# RobotCtrl_Base_Func.net
KiCad netlist of a schematic drawn in Altium Designer
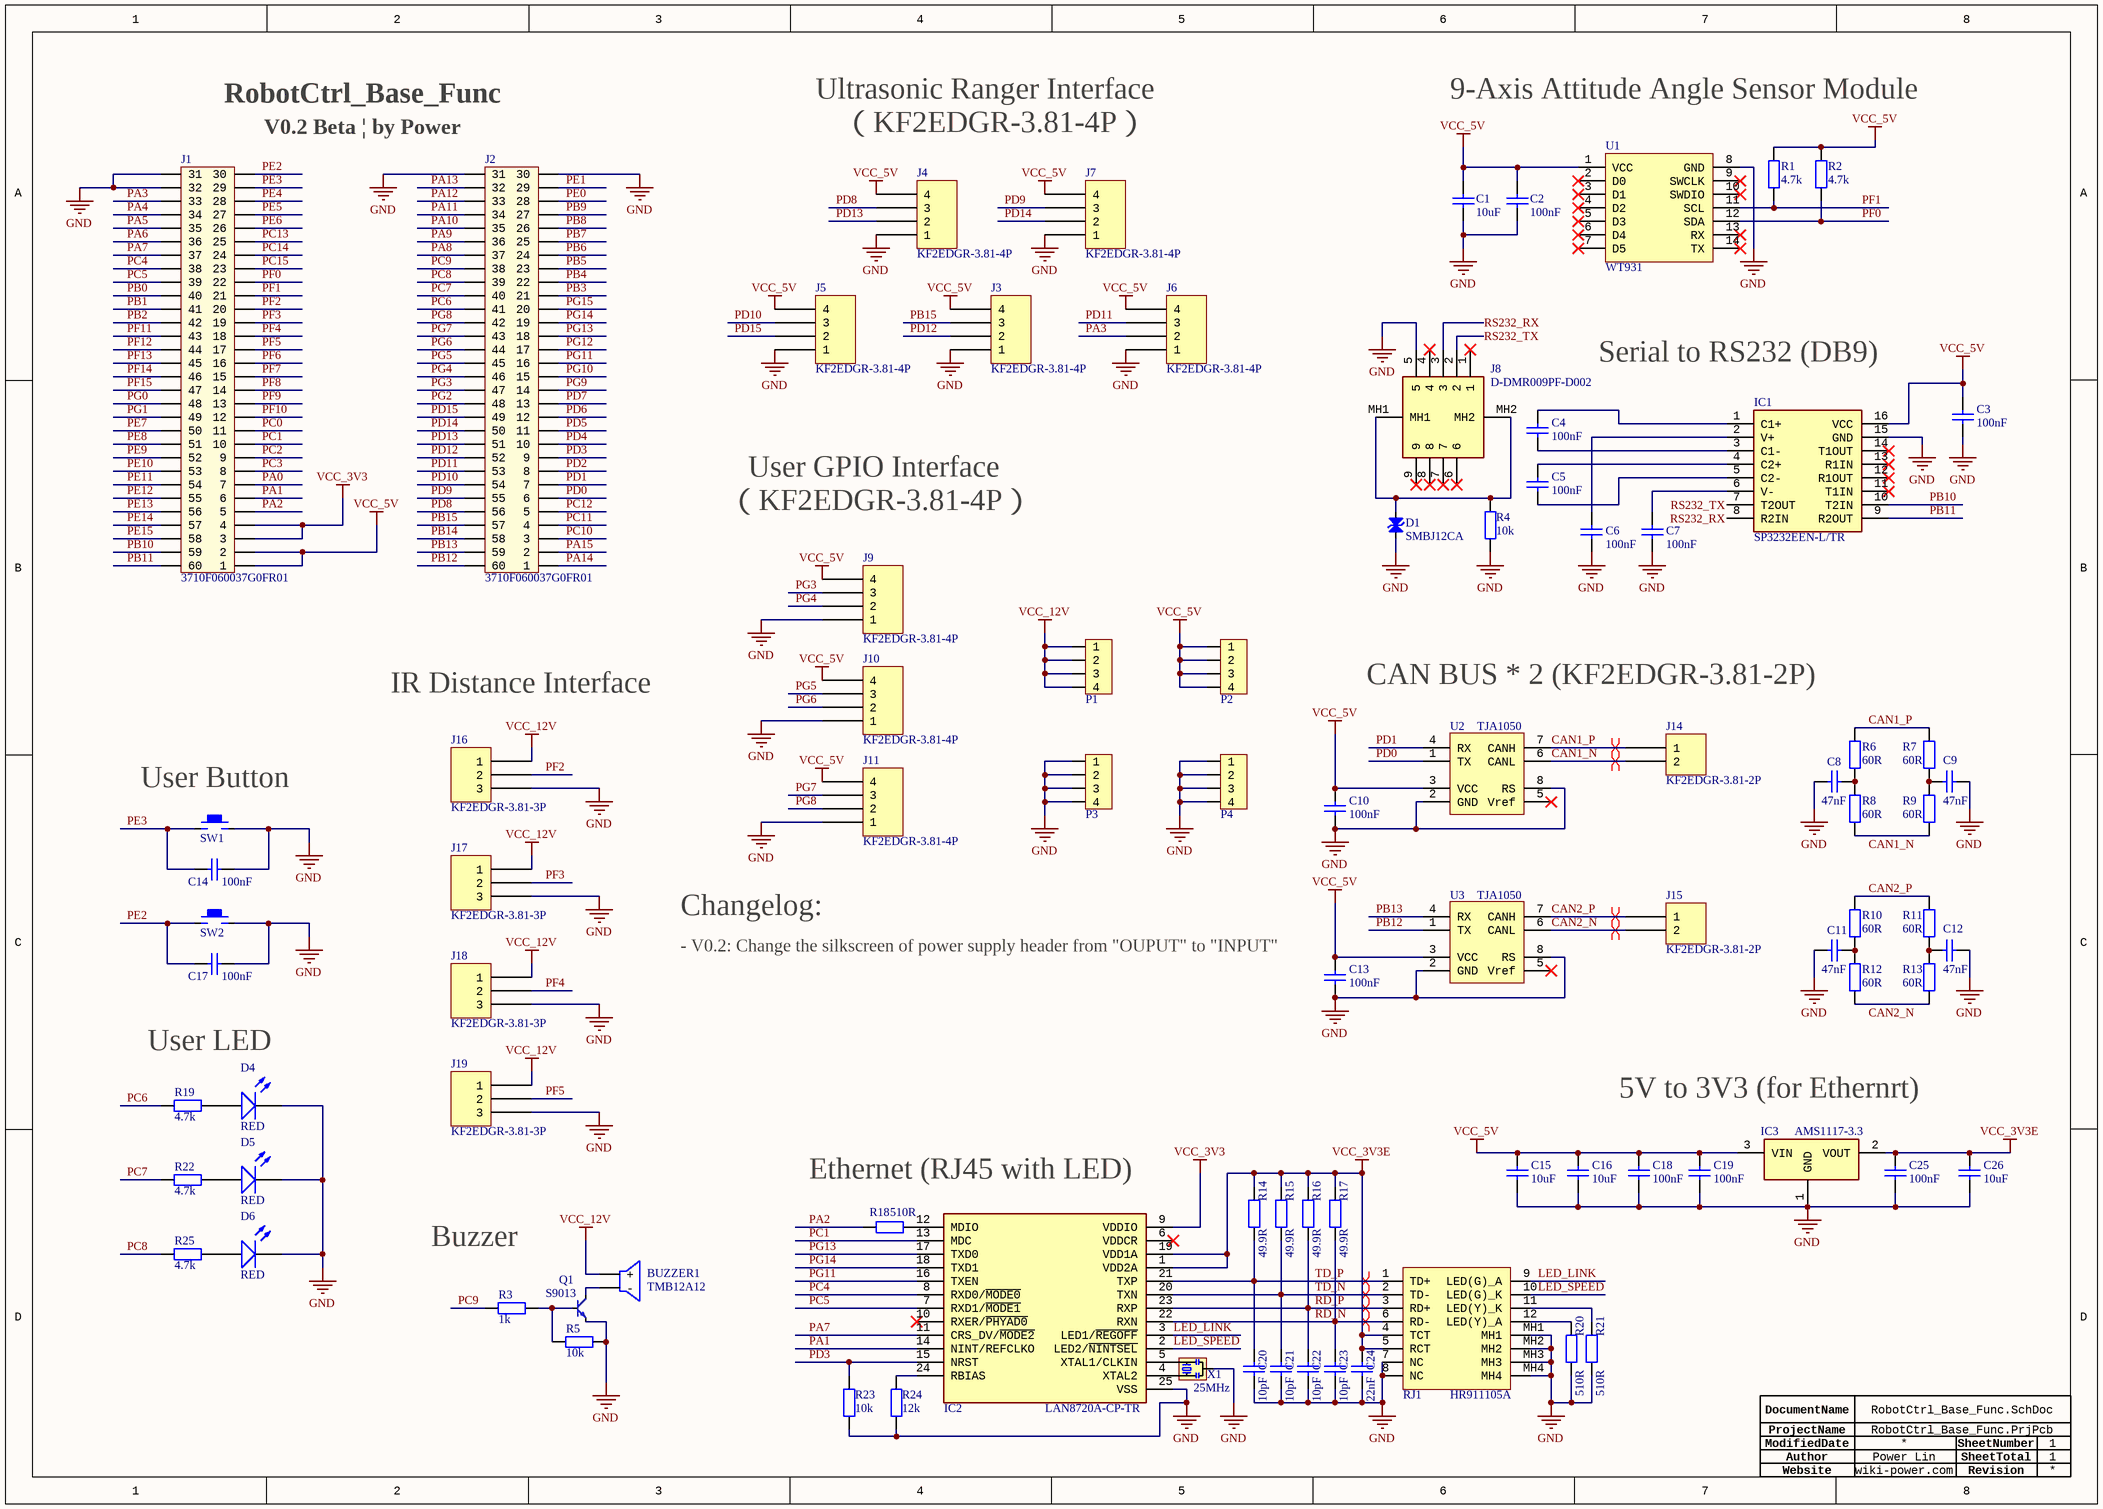
[diagram p0: RobotCtrl_Base_Func.SchDoc]

(export (version "E")
  (design (tool "Eeschema 10.0.6"))
  (components
    (comp (ref "BUZZER1")
      (value "TMB12A12")
      (footprint "DIP,P=7.6mm")
      (description "TMB12A12 有源蜂鸣器")
      (libsource (lib "Power_Lib_Altium") (part "BUZZER"))
    )
    (comp (ref "C1")
      (value "10uF")
      (footprint "CAP-0603")
      (description "贴片电容")
      (libsource (lib "Power_Lib_Altium") (part "CAP"))
    )
    (comp (ref "C2")
      (value "100nF")
      (footprint "CAP-0603")
      (description "贴片电容")
      (libsource (lib "Power_Lib_Altium") (part "CAP"))
    )
    (comp (ref "C3")
      (value "100nF")
      (footprint "CAP-0603")
      (description "贴片电容")
      (libsource (lib "Power_Lib_Altium") (part "CAP"))
    )
    (comp (ref "C4")
      (value "100nF")
      (footprint "CAP-0603")
      (description "贴片电容")
      (libsource (lib "Power_Lib_Altium") (part "CAP"))
    )
    (comp (ref "C5")
      (value "100nF")
      (footprint "CAP-0603")
      (description "贴片电容")
      (libsource (lib "Power_Lib_Altium") (part "CAP"))
    )
    (comp (ref "C6")
      (value "100nF")
      (footprint "CAP-0603")
      (description "贴片电容")
      (libsource (lib "Power_Lib_Altium") (part "CAP"))
    )
    (comp (ref "C7")
      (value "100nF")
      (footprint "CAP-0603")
      (description "贴片电容")
      (libsource (lib "Power_Lib_Altium") (part "CAP"))
    )
    (comp (ref "C8")
      (value "47nF")
      (footprint "CAP-0603")
      (description "贴片电容")
      (libsource (lib "Power_Lib_Altium") (part "CAP"))
    )
    (comp (ref "C9")
      (value "47nF")
      (footprint "CAP-0603")
      (description "贴片电容")
      (libsource (lib "Power_Lib_Altium") (part "CAP"))
    )
    (comp (ref "C10")
      (value "100nF")
      (footprint "CAP-0603")
      (description "贴片电容")
      (libsource (lib "Power_Lib_Altium") (part "CAP"))
    )
    (comp (ref "C11")
      (value "47nF")
      (footprint "CAP-0603")
      (description "贴片电容")
      (libsource (lib "Power_Lib_Altium") (part "CAP"))
    )
    (comp (ref "C12")
      (value "47nF")
      (footprint "CAP-0603")
      (description "贴片电容")
      (libsource (lib "Power_Lib_Altium") (part "CAP"))
    )
    (comp (ref "C13")
      (value "100nF")
      (footprint "CAP-0603")
      (description "贴片电容")
      (libsource (lib "Power_Lib_Altium") (part "CAP"))
    )
    (comp (ref "C14")
      (value "100nF")
      (footprint "CAP-0603")
      (description "贴片电容")
      (libsource (lib "Power_Lib_Altium") (part "CAP"))
    )
    (comp (ref "C15")
      (value "10uF")
      (footprint "CAP-0603")
      (description "贴片电容")
      (libsource (lib "Power_Lib_Altium") (part "CAP"))
    )
    (comp (ref "C16")
      (value "10uF")
      (footprint "CAP-0603")
      (description "贴片电容")
      (libsource (lib "Power_Lib_Altium") (part "CAP"))
    )
    (comp (ref "C17")
      (value "100nF")
      (footprint "CAP-0603")
      (description "贴片电容")
      (libsource (lib "Power_Lib_Altium") (part "CAP"))
    )
    (comp (ref "C18")
      (value "100nF")
      (footprint "CAP-0603")
      (description "贴片电容")
      (libsource (lib "Power_Lib_Altium") (part "CAP"))
    )
    (comp (ref "C19")
      (value "100nF")
      (footprint "CAP-0603")
      (description "贴片电容")
      (libsource (lib "Power_Lib_Altium") (part "CAP"))
    )
    (comp (ref "C20")
      (value "10pF")
      (footprint "CAP-0603")
      (description "贴片电容")
      (libsource (lib "Power_Lib_Altium") (part "CAP"))
    )
    (comp (ref "C21")
      (value "10pF")
      (footprint "CAP-0603")
      (description "贴片电容")
      (libsource (lib "Power_Lib_Altium") (part "CAP"))
    )
    (comp (ref "C22")
      (value "10pF")
      (footprint "CAP-0603")
      (description "贴片电容")
      (libsource (lib "Power_Lib_Altium") (part "CAP"))
    )
    (comp (ref "C23")
      (value "10pF")
      (footprint "CAP-0603")
      (description "贴片电容")
      (libsource (lib "Power_Lib_Altium") (part "CAP"))
    )
    (comp (ref "C24")
      (value "22nF")
      (footprint "CAP-0603")
      (description "贴片电容")
      (libsource (lib "Power_Lib_Altium") (part "CAP"))
    )
    (comp (ref "C25")
      (value "100nF")
      (footprint "CAP-0603")
      (description "贴片电容")
      (libsource (lib "Power_Lib_Altium") (part "CAP"))
    )
    (comp (ref "C26")
      (value "10uF")
      (footprint "CAP-0603")
      (description "贴片电容")
      (libsource (lib "Power_Lib_Altium") (part "CAP"))
    )
    (comp (ref "D1")
      (value "SMBJ12CA")
      (footprint "DO-214AA/SMB")
      (libsource (lib "Power_Lib_Altium") (part "TVS_C"))
    )
    (comp (ref "D4")
      (value "RED")
      (footprint "LED-0603")
      (description "发光二极管")
      (libsource (lib "Power_Lib_Altium") (part "LED"))
    )
    (comp (ref "D5")
      (value "RED")
      (footprint "LED-0603")
      (description "发光二极管")
      (libsource (lib "Power_Lib_Altium") (part "LED"))
    )
    (comp (ref "D6")
      (value "RED")
      (footprint "LED-0603")
      (description "发光二极管")
      (libsource (lib "Power_Lib_Altium") (part "LED"))
    )
    (comp (ref "IC1")
      (value "SP3232EEN-L/TR")
      (footprint "SOIC-16_150mil")
      (description "RS232 芯片")
      (fields (field (name "MOUSER PART NUMBER") "701-SP3232EEN-L/TR"))
      (libsource (lib "Power_Lib_Altium") (part "SP3232EEN"))
    )
    (comp (ref "IC2")
      (value "LAN8720A-CP-TR")
      (footprint "QFN-24-4x4")
      (description "Integrated Circuit")
      (fields (field (name "MOUSER PART NUMBER") "886-LAN8720A-CP-TR"))
      (libsource (lib "Power_Lib_Altium") (part "LAN8720A-CP-TR"))
    )
    (comp (ref "IC3")
      (value "AMS1117-3.3")
      (footprint "SOT-223")
      (description "AMS1117-3.3 1.0A")
      (fields (field (name "MANUFACTURER_PART_NUMBER") "SI2302DS") (field (name "RS PART NUMBER") "7983053P"))
      (libsource (lib "Power_Lib_Altium") (part "AMS1117"))
    )
    (comp (ref "J1")
      (value "3710F060037G0FR01")
      (footprint "3710M060037G3FT01")
      (description "B2B Connector")
      (libsource (lib "Power_Lib_Altium") (part "3710M/F"))
    )
    (comp (ref "J2")
      (value "3710F060037G0FR01")
      (footprint "3710M060037G3FT01")
      (description "B2B Connector")
      (libsource (lib "Power_Lib_Altium") (part "3710M/F"))
    )
    (comp (ref "J3")
      (value "KF2EDGR-3.81-4P")
      (footprint "FCI 06-381-4PIN")
      (description "TERM BLOCK HDR 4POS 90DEG 3.81MM")
      (fields (field (name "PART NUMBER") "OQ0432510000G") (field (name "MANUFACTURER") "Amphenol Anytek"))
      (libsource (lib "Power_Lib_Altium") (part "KF2EDGR-3.81-4P"))
    )
    (comp (ref "J4")
      (value "KF2EDGR-3.81-4P")
      (footprint "FCI 06-381-4PIN")
      (description "TERM BLOCK HDR 4POS 90DEG 3.81MM")
      (fields (field (name "PART NUMBER") "OQ0432510000G") (field (name "MANUFACTURER") "Amphenol Anytek"))
      (libsource (lib "Power_Lib_Altium") (part "KF2EDGR-3.81-4P"))
    )
    (comp (ref "J5")
      (value "KF2EDGR-3.81-4P")
      (footprint "FCI 06-381-4PIN")
      (description "TERM BLOCK HDR 4POS 90DEG 3.81MM")
      (fields (field (name "PART NUMBER") "OQ0432510000G") (field (name "MANUFACTURER") "Amphenol Anytek"))
      (libsource (lib "Power_Lib_Altium") (part "KF2EDGR-3.81-4P"))
    )
    (comp (ref "J6")
      (value "KF2EDGR-3.81-4P")
      (footprint "FCI 06-381-4PIN")
      (description "TERM BLOCK HDR 4POS 90DEG 3.81MM")
      (fields (field (name "PART NUMBER") "OQ0432510000G") (field (name "MANUFACTURER") "Amphenol Anytek"))
      (libsource (lib "Power_Lib_Altium") (part "KF2EDGR-3.81-4P"))
    )
    (comp (ref "J7")
      (value "KF2EDGR-3.81-4P")
      (footprint "FCI 06-381-4PIN")
      (description "TERM BLOCK HDR 4POS 90DEG 3.81MM")
      (fields (field (name "PART NUMBER") "OQ0432510000G") (field (name "MANUFACTURER") "Amphenol Anytek"))
      (libsource (lib "Power_Lib_Altium") (part "KF2EDGR-3.81-4P"))
    )
    (comp (ref "J8")
      (value "D-DMR009PF-D002")
      (footprint "Through Hole,P=2.77mm")
      (description "D-Sub 连接器")
      (fields
        (field (name "MANUFACTURER_PART_NUMBER") "5747844-5")
        (field (name "MOUSER PART NUMBER") "571-5747844-5")
      )
      (libsource (lib "Power_Lib_Altium") (part "DB9"))
    )
    (comp (ref "J9")
      (value "KF2EDGR-3.81-4P")
      (footprint "FCI 06-381-4PIN")
      (description "TERM BLOCK HDR 4POS 90DEG 3.81MM")
      (fields (field (name "PART NUMBER") "OQ0432510000G") (field (name "MANUFACTURER") "Amphenol Anytek"))
      (libsource (lib "Power_Lib_Altium") (part "KF2EDGR-3.81-4P"))
    )
    (comp (ref "J10")
      (value "KF2EDGR-3.81-4P")
      (footprint "FCI 06-381-4PIN")
      (description "TERM BLOCK HDR 4POS 90DEG 3.81MM")
      (fields (field (name "PART NUMBER") "OQ0432510000G") (field (name "MANUFACTURER") "Amphenol Anytek"))
      (libsource (lib "Power_Lib_Altium") (part "KF2EDGR-3.81-4P"))
    )
    (comp (ref "J11")
      (value "KF2EDGR-3.81-4P")
      (footprint "FCI 06-381-4PIN")
      (description "TERM BLOCK HDR 4POS 90DEG 3.81MM")
      (fields (field (name "PART NUMBER") "OQ0432510000G") (field (name "MANUFACTURER") "Amphenol Anytek"))
      (libsource (lib "Power_Lib_Altium") (part "KF2EDGR-3.81-4P"))
    )
    (comp (ref "J14")
      (value "KF2EDGR-3.81-2P")
      (footprint "FCI 06-381-2PIN")
      (description "TERM BLOCK HDR 2POS 90DEG 3.81MM")
      (fields (field (name "PART NUMBER") "OQ0232510000G") (field (name "MANUFACTURER") "Amphenol Anytek"))
      (libsource (lib "Power_Lib_Altium") (part "KF2EDGR-3.81-2P"))
    )
    (comp (ref "J15")
      (value "KF2EDGR-3.81-2P")
      (footprint "FCI 06-381-2PIN")
      (description "TERM BLOCK HDR 2POS 90DEG 3.81MM")
      (fields (field (name "PART NUMBER") "OQ0232510000G") (field (name "MANUFACTURER") "Amphenol Anytek"))
      (libsource (lib "Power_Lib_Altium") (part "KF2EDGR-3.81-2P"))
    )
    (comp (ref "J16")
      (value "KF2EDGR-3.81-3P")
      (footprint "FCI 06-381-3PIN")
      (description "TERM BLOCK HDR 3POS 90DEG 3.81MM")
      (fields (field (name "MANUFACTURER") "Amphenol Anytek") (field (name "PART NUMBER") "OQ0332510000G"))
      (libsource (lib "Power_Lib_Altium") (part "KF2EDGR-3.81-3P"))
    )
    (comp (ref "J17")
      (value "KF2EDGR-3.81-3P")
      (footprint "FCI 06-381-3PIN")
      (description "TERM BLOCK HDR 3POS 90DEG 3.81MM")
      (fields (field (name "MANUFACTURER") "Amphenol Anytek") (field (name "PART NUMBER") "OQ0332510000G"))
      (libsource (lib "Power_Lib_Altium") (part "KF2EDGR-3.81-3P"))
    )
    (comp (ref "J18")
      (value "KF2EDGR-3.81-3P")
      (footprint "FCI 06-381-3PIN")
      (description "TERM BLOCK HDR 3POS 90DEG 3.81MM")
      (fields (field (name "MANUFACTURER") "Amphenol Anytek") (field (name "PART NUMBER") "OQ0332510000G"))
      (libsource (lib "Power_Lib_Altium") (part "KF2EDGR-3.81-3P"))
    )
    (comp (ref "J19")
      (value "KF2EDGR-3.81-3P")
      (footprint "FCI 06-381-3PIN")
      (description "TERM BLOCK HDR 3POS 90DEG 3.81MM")
      (fields (field (name "MANUFACTURER") "Amphenol Anytek") (field (name "PART NUMBER") "OQ0332510000G"))
      (libsource (lib "Power_Lib_Altium") (part "KF2EDGR-3.81-3P"))
    )
    (comp (ref "P1")
      (value "HDR1x4_2.54")
      (footprint "HDR1X4_2.54")
      (description "Header")
      (libsource (lib "Power_Lib_Altium") (part "HDR1x4_2.54"))
    )
    (comp (ref "P2")
      (value "HDR1x4_2.54")
      (footprint "HDR1X4_2.54")
      (description "Header")
      (libsource (lib "Power_Lib_Altium") (part "HDR1x4_2.54"))
    )
    (comp (ref "P3")
      (value "HDR1x4_2.54")
      (footprint "HDR1X4_2.54")
      (description "Header")
      (libsource (lib "Power_Lib_Altium") (part "HDR1x4_2.54"))
    )
    (comp (ref "P4")
      (value "HDR1x4_2.54")
      (footprint "HDR1X4_2.54")
      (description "Header")
      (libsource (lib "Power_Lib_Altium") (part "HDR1x4_2.54"))
    )
    (comp (ref "Q1")
      (value "S9013")
      (footprint "SOT-23-3")
      (libsource (lib "Power_Lib_Altium") (part "BJT_NPN"))
    )
    (comp (ref "R1")
      (value "4.7k")
      (footprint "R-0603")
      (description "贴片电阻")
      (libsource (lib "Power_Lib_Altium") (part "RES"))
    )
    (comp (ref "R2")
      (value "4.7k")
      (footprint "R-0603")
      (description "贴片电阻")
      (libsource (lib "Power_Lib_Altium") (part "RES"))
    )
    (comp (ref "R3")
      (value "1k")
      (footprint "R-0603")
      (description "贴片电阻")
      (libsource (lib "") (part "RES_3"))
    )
    (comp (ref "R4")
      (value "10k")
      (footprint "R-0603")
      (description "贴片电阻")
      (libsource (lib "Power_Lib_Altium") (part "RES"))
    )
    (comp (ref "R5")
      (value "10k")
      (footprint "R-0603")
      (description "贴片电阻")
      (libsource (lib "") (part "RES_2"))
    )
    (comp (ref "R6")
      (value "60R")
      (footprint "R-0603")
      (description "贴片电阻")
      (libsource (lib "") (part "RES_1"))
    )
    (comp (ref "R7")
      (value "60R")
      (footprint "R-0603")
      (description "贴片电阻")
      (libsource (lib "Power_Lib_Altium") (part "RES"))
    )
    (comp (ref "R8")
      (value "60R")
      (footprint "R-0603")
      (description "贴片电阻")
      (libsource (lib "") (part "RES_1"))
    )
    (comp (ref "R9")
      (value "60R")
      (footprint "R-0603")
      (description "贴片电阻")
      (libsource (lib "Power_Lib_Altium") (part "RES"))
    )
    (comp (ref "R10")
      (value "60R")
      (footprint "R-0603")
      (description "贴片电阻")
      (libsource (lib "") (part "RES_1"))
    )
    (comp (ref "R11")
      (value "60R")
      (footprint "R-0603")
      (description "贴片电阻")
      (libsource (lib "Power_Lib_Altium") (part "RES"))
    )
    (comp (ref "R12")
      (value "60R")
      (footprint "R-0603")
      (description "贴片电阻")
      (libsource (lib "") (part "RES_1"))
    )
    (comp (ref "R13")
      (value "60R")
      (footprint "R-0603")
      (description "贴片电阻")
      (libsource (lib "Power_Lib_Altium") (part "RES"))
    )
    (comp (ref "R14")
      (value "49.9R")
      (footprint "R-0603")
      (description "贴片电阻")
      (libsource (lib "Power_Lib_Altium") (part "RES"))
    )
    (comp (ref "R15")
      (value "49.9R")
      (footprint "R-0603")
      (description "贴片电阻")
      (libsource (lib "Power_Lib_Altium") (part "RES"))
    )
    (comp (ref "R16")
      (value "49.9R")
      (footprint "R-0603")
      (description "贴片电阻")
      (libsource (lib "Power_Lib_Altium") (part "RES"))
    )
    (comp (ref "R17")
      (value "49.9R")
      (footprint "R-0603")
      (description "贴片电阻")
      (libsource (lib "Power_Lib_Altium") (part "RES"))
    )
    (comp (ref "R18")
      (value "510R")
      (footprint "R-0603")
      (description "贴片电阻")
      (libsource (lib "") (part "RES_2"))
    )
    (comp (ref "R19")
      (value "4.7k")
      (footprint "R-0603")
      (description "贴片电阻")
      (libsource (lib "") (part "RES_2"))
    )
    (comp (ref "R20")
      (value "510R")
      (footprint "R-0603")
      (description "贴片电阻")
      (libsource (lib "Power_Lib_Altium") (part "RES"))
    )
    (comp (ref "R21")
      (value "510R")
      (footprint "R-0603")
      (description "贴片电阻")
      (libsource (lib "Power_Lib_Altium") (part "RES"))
    )
    (comp (ref "R22")
      (value "4.7k")
      (footprint "R-0603")
      (description "贴片电阻")
      (libsource (lib "") (part "RES_2"))
    )
    (comp (ref "R23")
      (value "10k")
      (footprint "R-0603")
      (description "贴片电阻")
      (libsource (lib "") (part "RES_1"))
    )
    (comp (ref "R24")
      (value "12k")
      (footprint "R-0603")
      (description "贴片电阻")
      (libsource (lib "") (part "RES_1"))
    )
    (comp (ref "R25")
      (value "4.7k")
      (footprint "R-0603")
      (description "贴片电阻")
      (libsource (lib "") (part "RES_2"))
    )
    (comp (ref "RJ1")
      (value "HR911105A")
      (footprint "HR911105A")
      (description "内置变压器的RJ45")
      (libsource (lib "Power_Lib_Altium") (part "RJ45_LED"))
    )
    (comp (ref "SW1")
      (value "KEY")
      (footprint "KEY-4P-4.2*3.4*2.5")
      (description "按键开关")
      (libsource (lib "Power_Lib_Altium") (part "KEY"))
    )
    (comp (ref "SW2")
      (value "KEY")
      (footprint "KEY-4P-4.2*3.4*2.5")
      (description "按键开关")
      (libsource (lib "Power_Lib_Altium") (part "KEY"))
    )
    (comp (ref "U1")
      (value "WT931")
      (footprint "WT931")
      (description "陀螺仪模组")
      (libsource (lib "Power_Lib_Altium") (part "WT931"))
    )
    (comp (ref "U2")
      (value "TJA1050")
      (footprint "SOIC_8")
      (description "CAN 控制器（5V）")
      (libsource (lib "Power_Lib_Altium") (part "TJA1050"))
    )
    (comp (ref "U3")
      (value "TJA1050")
      (footprint "SOIC_8")
      (description "CAN 控制器（5V）")
      (libsource (lib "Power_Lib_Altium") (part "TJA1050"))
    )
    (comp (ref "X1")
      (value "25MHz")
      (footprint "SMD3213-3P")
      (description "CSTCE25M00G51-R0")
      (libsource (lib "Power_Lib_Altium") (part "XTAL"))
    )
  )
  (nets
    (net (code "1") (name "/CAN1_N") (class "Default")
      (node (ref "J14") (pin "2") (pinfunction "2_2") (pintype "passive"))
      (node (ref "R8") (pin "2") (pinfunction "2_2") (pintype "passive"))
      (node (ref "R9") (pin "1") (pinfunction "1_1") (pintype "passive"))
      (node (ref "U2") (pin "6") (pinfunction "CANL_6") (pintype "passive"))
    )
    (net (code "2") (name "/CAN1_P") (class "Default")
      (node (ref "J14") (pin "1") (pinfunction "1_1") (pintype "passive"))
      (node (ref "R6") (pin "1") (pinfunction "1_1") (pintype "passive"))
      (node (ref "R7") (pin "2") (pinfunction "2_2") (pintype "passive"))
      (node (ref "U2") (pin "7") (pinfunction "CANH_7") (pintype "passive"))
    )
    (net (code "3") (name "/CAN2_N") (class "Default")
      (node (ref "J15") (pin "2") (pinfunction "2_2") (pintype "passive"))
      (node (ref "R12") (pin "2") (pinfunction "2_2") (pintype "passive"))
      (node (ref "R13") (pin "1") (pinfunction "1_1") (pintype "passive"))
      (node (ref "U3") (pin "6") (pinfunction "CANL_6") (pintype "passive"))
    )
    (net (code "4") (name "/CAN2_P") (class "Default")
      (node (ref "J15") (pin "1") (pinfunction "1_1") (pintype "passive"))
      (node (ref "R10") (pin "1") (pinfunction "1_1") (pintype "passive"))
      (node (ref "R11") (pin "2") (pinfunction "2_2") (pintype "passive"))
      (node (ref "U3") (pin "7") (pinfunction "CANH_7") (pintype "passive"))
    )
    (net (code "5") (name "/LED_LINK") (class "Default")
      (node (ref "IC2") (pin "3") (pinfunction "LED1/~{REGOFF}_3") (pintype "passive"))
      (node (ref "RJ1") (pin "9") (pinfunction "LED(G)_A_9") (pintype "passive"))
    )
    (net (code "6") (name "/LED_SPEED") (class "Default")
      (node (ref "IC2") (pin "2") (pinfunction "LED2/~{NINTSEL}_2") (pintype "passive"))
      (node (ref "RJ1") (pin "10") (pinfunction "LED(G)_K_10") (pintype "passive"))
    )
    (net (code "7") (name "/PA0") (class "Default")
      (node (ref "J1") (pin "7") (pinfunction "7_7") (pintype "passive"))
    )
    (net (code "8") (name "/PA1") (class "Default")
      (node (ref "IC2") (pin "14") (pinfunction "NINT/REFCLKO_14") (pintype "passive"))
      (node (ref "J1") (pin "6") (pinfunction "6_6") (pintype "passive"))
    )
    (net (code "9") (name "/PA2") (class "Default")
      (node (ref "J1") (pin "5") (pinfunction "5_5") (pintype "passive"))
      (node (ref "R18") (pin "2") (pinfunction "2_2") (pintype "passive"))
    )
    (net (code "10") (name "/PA3") (class "Default")
      (node (ref "J1") (pin "33") (pinfunction "33_33") (pintype "passive"))
      (node (ref "J6") (pin "2") (pinfunction "2_2") (pintype "passive"))
    )
    (net (code "11") (name "/PA4") (class "Default")
      (node (ref "J1") (pin "34") (pinfunction "34_34") (pintype "passive"))
    )
    (net (code "12") (name "/PA5") (class "Default")
      (node (ref "J1") (pin "35") (pinfunction "35_35") (pintype "passive"))
    )
    (net (code "13") (name "/PA6") (class "Default")
      (node (ref "J1") (pin "36") (pinfunction "36_36") (pintype "passive"))
    )
    (net (code "14") (name "/PA7") (class "Default")
      (node (ref "IC2") (pin "11") (pinfunction "CRS_DV/~{MODE2}_11") (pintype "passive"))
      (node (ref "J1") (pin "37") (pinfunction "37_37") (pintype "passive"))
    )
    (net (code "15") (name "/PA8") (class "Default")
      (node (ref "J2") (pin "37") (pinfunction "37_37") (pintype "passive"))
    )
    (net (code "16") (name "/PA9") (class "Default")
      (node (ref "J2") (pin "36") (pinfunction "36_36") (pintype "passive"))
    )
    (net (code "17") (name "/PA10") (class "Default")
      (node (ref "J2") (pin "35") (pinfunction "35_35") (pintype "passive"))
    )
    (net (code "18") (name "/PA11") (class "Default")
      (node (ref "J2") (pin "34") (pinfunction "34_34") (pintype "passive"))
    )
    (net (code "19") (name "/PA12") (class "Default")
      (node (ref "J2") (pin "33") (pinfunction "33_33") (pintype "passive"))
    )
    (net (code "20") (name "/PA13") (class "Default")
      (node (ref "J2") (pin "32") (pinfunction "32_32") (pintype "passive"))
    )
    (net (code "21") (name "/PA14") (class "Default")
      (node (ref "J2") (pin "1") (pinfunction "1_1") (pintype "passive"))
    )
    (net (code "22") (name "/PA15") (class "Default")
      (node (ref "J2") (pin "2") (pinfunction "2_2") (pintype "passive"))
    )
    (net (code "23") (name "/PB0") (class "Default")
      (node (ref "J1") (pin "40") (pinfunction "40_40") (pintype "passive"))
    )
    (net (code "24") (name "/PB1") (class "Default")
      (node (ref "J1") (pin "41") (pinfunction "41_41") (pintype "passive"))
    )
    (net (code "25") (name "/PB2") (class "Default")
      (node (ref "J1") (pin "42") (pinfunction "42_42") (pintype "passive"))
    )
    (net (code "26") (name "/PB3") (class "Default")
      (node (ref "J2") (pin "21") (pinfunction "21_21") (pintype "passive"))
    )
    (net (code "27") (name "/PB4") (class "Default")
      (node (ref "J2") (pin "22") (pinfunction "22_22") (pintype "passive"))
    )
    (net (code "28") (name "/PB5") (class "Default")
      (node (ref "J2") (pin "23") (pinfunction "23_23") (pintype "passive"))
    )
    (net (code "29") (name "/PB6") (class "Default")
      (node (ref "J2") (pin "24") (pinfunction "24_24") (pintype "passive"))
    )
    (net (code "30") (name "/PB7") (class "Default")
      (node (ref "J2") (pin "25") (pinfunction "25_25") (pintype "passive"))
    )
    (net (code "31") (name "/PB8") (class "Default")
      (node (ref "J2") (pin "26") (pinfunction "26_26") (pintype "passive"))
    )
    (net (code "32") (name "/PB9") (class "Default")
      (node (ref "J2") (pin "27") (pinfunction "27_27") (pintype "passive"))
    )
    (net (code "33") (name "/PB10") (class "Default")
      (node (ref "IC1") (pin "10") (pinfunction "T2IN_10") (pintype "passive"))
      (node (ref "J1") (pin "59") (pinfunction "59_59") (pintype "passive"))
    )
    (net (code "34") (name "/PB11") (class "Default")
      (node (ref "IC1") (pin "9") (pinfunction "R2OUT_9") (pintype "passive"))
      (node (ref "J1") (pin "60") (pinfunction "60_60") (pintype "passive"))
    )
    (net (code "35") (name "/PB12") (class "Default")
      (node (ref "J2") (pin "60") (pinfunction "60_60") (pintype "passive"))
      (node (ref "U3") (pin "1") (pinfunction "TX_1") (pintype "passive"))
    )
    (net (code "36") (name "/PB13") (class "Default")
      (node (ref "J2") (pin "59") (pinfunction "59_59") (pintype "passive"))
      (node (ref "U3") (pin "4") (pinfunction "RX_4") (pintype "passive"))
    )
    (net (code "37") (name "/PB14") (class "Default")
      (node (ref "J2") (pin "58") (pinfunction "58_58") (pintype "passive"))
    )
    (net (code "38") (name "/PB15") (class "Default")
      (node (ref "J2") (pin "57") (pinfunction "57_57") (pintype "passive"))
      (node (ref "J3") (pin "3") (pinfunction "3_3") (pintype "passive"))
    )
    (net (code "39") (name "/PC0") (class "Default")
      (node (ref "J1") (pin "11") (pinfunction "11_11") (pintype "passive"))
    )
    (net (code "40") (name "/PC1") (class "Default")
      (node (ref "IC2") (pin "13") (pinfunction "MDC_13") (pintype "passive"))
      (node (ref "J1") (pin "10") (pinfunction "10_10") (pintype "passive"))
    )
    (net (code "41") (name "/PC2") (class "Default")
      (node (ref "J1") (pin "9") (pinfunction "9_9") (pintype "passive"))
    )
    (net (code "42") (name "/PC3") (class "Default")
      (node (ref "J1") (pin "8") (pinfunction "8_8") (pintype "passive"))
    )
    (net (code "43") (name "/PC4") (class "Default")
      (node (ref "IC2") (pin "8") (pinfunction "RXD0/~{MODE0}_8") (pintype "passive"))
      (node (ref "J1") (pin "38") (pinfunction "38_38") (pintype "passive"))
    )
    (net (code "44") (name "/PC5") (class "Default")
      (node (ref "IC2") (pin "7") (pinfunction "RXD1/~{MODE1}_7") (pintype "passive"))
      (node (ref "J1") (pin "39") (pinfunction "39_39") (pintype "passive"))
    )
    (net (code "45") (name "/PC6") (class "Default")
      (node (ref "J2") (pin "41") (pinfunction "41_41") (pintype "passive"))
      (node (ref "R19") (pin "2") (pinfunction "2_2") (pintype "passive"))
    )
    (net (code "46") (name "/PC7") (class "Default")
      (node (ref "J2") (pin "40") (pinfunction "40_40") (pintype "passive"))
      (node (ref "R22") (pin "2") (pinfunction "2_2") (pintype "passive"))
    )
    (net (code "47") (name "/PC8") (class "Default")
      (node (ref "J2") (pin "39") (pinfunction "39_39") (pintype "passive"))
      (node (ref "R25") (pin "2") (pinfunction "2_2") (pintype "passive"))
    )
    (net (code "48") (name "/PC9") (class "Default")
      (node (ref "J2") (pin "38") (pinfunction "38_38") (pintype "passive"))
      (node (ref "R3") (pin "1") (pinfunction "1_1") (pintype "passive"))
    )
    (net (code "49") (name "/PC10") (class "Default")
      (node (ref "J2") (pin "3") (pinfunction "3_3") (pintype "passive"))
    )
    (net (code "50") (name "/PC11") (class "Default")
      (node (ref "J2") (pin "4") (pinfunction "4_4") (pintype "passive"))
    )
    (net (code "51") (name "/PC12") (class "Default")
      (node (ref "J2") (pin "5") (pinfunction "5_5") (pintype "passive"))
    )
    (net (code "52") (name "/PC13") (class "Default")
      (node (ref "J1") (pin "25") (pinfunction "25_25") (pintype "passive"))
    )
    (net (code "53") (name "/PC14") (class "Default")
      (node (ref "J1") (pin "24") (pinfunction "24_24") (pintype "passive"))
    )
    (net (code "54") (name "/PC15") (class "Default")
      (node (ref "J1") (pin "23") (pinfunction "23_23") (pintype "passive"))
    )
    (net (code "55") (name "/PD0") (class "Default")
      (node (ref "J2") (pin "6") (pinfunction "6_6") (pintype "passive"))
      (node (ref "U2") (pin "1") (pinfunction "TX_1") (pintype "passive"))
    )
    (net (code "56") (name "/PD1") (class "Default")
      (node (ref "J2") (pin "7") (pinfunction "7_7") (pintype "passive"))
      (node (ref "U2") (pin "4") (pinfunction "RX_4") (pintype "passive"))
    )
    (net (code "57") (name "/PD2") (class "Default")
      (node (ref "J2") (pin "8") (pinfunction "8_8") (pintype "passive"))
    )
    (net (code "58") (name "/PD3") (class "Default")
      (node (ref "IC2") (pin "15") (pinfunction "NRST_15") (pintype "passive"))
      (node (ref "J2") (pin "9") (pinfunction "9_9") (pintype "passive"))
      (node (ref "R23") (pin "1") (pinfunction "1_1") (pintype "passive"))
    )
    (net (code "59") (name "/PD4") (class "Default")
      (node (ref "J2") (pin "10") (pinfunction "10_10") (pintype "passive"))
    )
    (net (code "60") (name "/PD5") (class "Default")
      (node (ref "J2") (pin "11") (pinfunction "11_11") (pintype "passive"))
    )
    (net (code "61") (name "/PD6") (class "Default")
      (node (ref "J2") (pin "12") (pinfunction "12_12") (pintype "passive"))
    )
    (net (code "62") (name "/PD7") (class "Default")
      (node (ref "J2") (pin "13") (pinfunction "13_13") (pintype "passive"))
    )
    (net (code "63") (name "/PD8") (class "Default")
      (node (ref "J2") (pin "56") (pinfunction "56_56") (pintype "passive"))
      (node (ref "J4") (pin "3") (pinfunction "3_3") (pintype "passive"))
    )
    (net (code "64") (name "/PD9") (class "Default")
      (node (ref "J2") (pin "55") (pinfunction "55_55") (pintype "passive"))
      (node (ref "J7") (pin "3") (pinfunction "3_3") (pintype "passive"))
    )
    (net (code "65") (name "/PD10") (class "Default")
      (node (ref "J2") (pin "54") (pinfunction "54_54") (pintype "passive"))
      (node (ref "J5") (pin "3") (pinfunction "3_3") (pintype "passive"))
    )
    (net (code "66") (name "/PD11") (class "Default")
      (node (ref "J2") (pin "53") (pinfunction "53_53") (pintype "passive"))
      (node (ref "J6") (pin "3") (pinfunction "3_3") (pintype "passive"))
    )
    (net (code "67") (name "/PD12") (class "Default")
      (node (ref "J2") (pin "52") (pinfunction "52_52") (pintype "passive"))
      (node (ref "J3") (pin "2") (pinfunction "2_2") (pintype "passive"))
    )
    (net (code "68") (name "/PD13") (class "Default")
      (node (ref "J2") (pin "51") (pinfunction "51_51") (pintype "passive"))
      (node (ref "J4") (pin "2") (pinfunction "2_2") (pintype "passive"))
    )
    (net (code "69") (name "/PD14") (class "Default")
      (node (ref "J2") (pin "50") (pinfunction "50_50") (pintype "passive"))
      (node (ref "J7") (pin "2") (pinfunction "2_2") (pintype "passive"))
    )
    (net (code "70") (name "/PD15") (class "Default")
      (node (ref "J2") (pin "49") (pinfunction "49_49") (pintype "passive"))
      (node (ref "J5") (pin "2") (pinfunction "2_2") (pintype "passive"))
    )
    (net (code "71") (name "/PE0") (class "Default")
      (node (ref "J2") (pin "28") (pinfunction "28_28") (pintype "passive"))
    )
    (net (code "72") (name "/PE1") (class "Default")
      (node (ref "J2") (pin "29") (pinfunction "29_29") (pintype "passive"))
    )
    (net (code "73") (name "/PE2") (class "Default")
      (node (ref "C17") (pin "2") (pinfunction "2_2") (pintype "passive"))
      (node (ref "J1") (pin "30") (pinfunction "30_30") (pintype "passive"))
      (node (ref "SW2") (pin "1") (pinfunction "1_1") (pintype "passive"))
    )
    (net (code "74") (name "/PE3") (class "Default")
      (node (ref "C14") (pin "2") (pinfunction "2_2") (pintype "passive"))
      (node (ref "J1") (pin "29") (pinfunction "29_29") (pintype "passive"))
      (node (ref "SW1") (pin "1") (pinfunction "1_1") (pintype "passive"))
    )
    (net (code "75") (name "/PE4") (class "Default")
      (node (ref "J1") (pin "28") (pinfunction "28_28") (pintype "passive"))
    )
    (net (code "76") (name "/PE5") (class "Default")
      (node (ref "J1") (pin "27") (pinfunction "27_27") (pintype "passive"))
    )
    (net (code "77") (name "/PE6") (class "Default")
      (node (ref "J1") (pin "26") (pinfunction "26_26") (pintype "passive"))
    )
    (net (code "78") (name "/PE7") (class "Default")
      (node (ref "J1") (pin "50") (pinfunction "50_50") (pintype "passive"))
    )
    (net (code "79") (name "/PE8") (class "Default")
      (node (ref "J1") (pin "51") (pinfunction "51_51") (pintype "passive"))
    )
    (net (code "80") (name "/PE9") (class "Default")
      (node (ref "J1") (pin "52") (pinfunction "52_52") (pintype "passive"))
    )
    (net (code "81") (name "/PE10") (class "Default")
      (node (ref "J1") (pin "53") (pinfunction "53_53") (pintype "passive"))
    )
    (net (code "82") (name "/PE11") (class "Default")
      (node (ref "J1") (pin "54") (pinfunction "54_54") (pintype "passive"))
    )
    (net (code "83") (name "/PE12") (class "Default")
      (node (ref "J1") (pin "55") (pinfunction "55_55") (pintype "passive"))
    )
    (net (code "84") (name "/PE13") (class "Default")
      (node (ref "J1") (pin "56") (pinfunction "56_56") (pintype "passive"))
    )
    (net (code "85") (name "/PE14") (class "Default")
      (node (ref "J1") (pin "57") (pinfunction "57_57") (pintype "passive"))
    )
    (net (code "86") (name "/PE15") (class "Default")
      (node (ref "J1") (pin "58") (pinfunction "58_58") (pintype "passive"))
    )
    (net (code "87") (name "/PF0") (class "Default")
      (node (ref "J1") (pin "22") (pinfunction "22_22") (pintype "passive"))
      (node (ref "R2") (pin "1") (pinfunction "1_1") (pintype "passive"))
      (node (ref "U1") (pin "12") (pinfunction "SDA_12") (pintype "passive"))
    )
    (net (code "88") (name "/PF1") (class "Default")
      (node (ref "J1") (pin "21") (pinfunction "21_21") (pintype "passive"))
      (node (ref "R1") (pin "1") (pinfunction "1_1") (pintype "passive"))
      (node (ref "U1") (pin "11") (pinfunction "SCL_11") (pintype "passive"))
    )
    (net (code "89") (name "/PF2") (class "Default")
      (node (ref "J1") (pin "20") (pinfunction "20_20") (pintype "passive"))
      (node (ref "J16") (pin "2") (pinfunction "2_2") (pintype "passive"))
    )
    (net (code "90") (name "/PF3") (class "Default")
      (node (ref "J1") (pin "19") (pinfunction "19_19") (pintype "passive"))
      (node (ref "J17") (pin "2") (pinfunction "2_2") (pintype "passive"))
    )
    (net (code "91") (name "/PF4") (class "Default")
      (node (ref "J1") (pin "18") (pinfunction "18_18") (pintype "passive"))
      (node (ref "J18") (pin "2") (pinfunction "2_2") (pintype "passive"))
    )
    (net (code "92") (name "/PF5") (class "Default")
      (node (ref "J1") (pin "17") (pinfunction "17_17") (pintype "passive"))
      (node (ref "J19") (pin "2") (pinfunction "2_2") (pintype "passive"))
    )
    (net (code "93") (name "/PF6") (class "Default")
      (node (ref "J1") (pin "16") (pinfunction "16_16") (pintype "passive"))
    )
    (net (code "94") (name "/PF7") (class "Default")
      (node (ref "J1") (pin "15") (pinfunction "15_15") (pintype "passive"))
    )
    (net (code "95") (name "/PF8") (class "Default")
      (node (ref "J1") (pin "14") (pinfunction "14_14") (pintype "passive"))
    )
    (net (code "96") (name "/PF9") (class "Default")
      (node (ref "J1") (pin "13") (pinfunction "13_13") (pintype "passive"))
    )
    (net (code "97") (name "/PF10") (class "Default")
      (node (ref "J1") (pin "12") (pinfunction "12_12") (pintype "passive"))
    )
    (net (code "98") (name "/PF11") (class "Default")
      (node (ref "J1") (pin "43") (pinfunction "43_43") (pintype "passive"))
    )
    (net (code "99") (name "/PF12") (class "Default")
      (node (ref "J1") (pin "44") (pinfunction "44_44") (pintype "passive"))
    )
    (net (code "100") (name "/PF13") (class "Default")
      (node (ref "J1") (pin "45") (pinfunction "45_45") (pintype "passive"))
    )
    (net (code "101") (name "/PF14") (class "Default")
      (node (ref "J1") (pin "46") (pinfunction "46_46") (pintype "passive"))
    )
    (net (code "102") (name "/PF15") (class "Default")
      (node (ref "J1") (pin "47") (pinfunction "47_47") (pintype "passive"))
    )
    (net (code "103") (name "/PG0") (class "Default")
      (node (ref "J1") (pin "48") (pinfunction "48_48") (pintype "passive"))
    )
    (net (code "104") (name "/PG1") (class "Default")
      (node (ref "J1") (pin "49") (pinfunction "49_49") (pintype "passive"))
    )
    (net (code "105") (name "/PG2") (class "Default")
      (node (ref "J2") (pin "48") (pinfunction "48_48") (pintype "passive"))
    )
    (net (code "106") (name "/PG3") (class "Default")
      (node (ref "J2") (pin "47") (pinfunction "47_47") (pintype "passive"))
      (node (ref "J9") (pin "3") (pinfunction "3_3") (pintype "passive"))
    )
    (net (code "107") (name "/PG4") (class "Default")
      (node (ref "J2") (pin "46") (pinfunction "46_46") (pintype "passive"))
      (node (ref "J9") (pin "2") (pinfunction "2_2") (pintype "passive"))
    )
    (net (code "108") (name "/PG5") (class "Default")
      (node (ref "J10") (pin "3") (pinfunction "3_3") (pintype "passive"))
      (node (ref "J2") (pin "45") (pinfunction "45_45") (pintype "passive"))
    )
    (net (code "109") (name "/PG6") (class "Default")
      (node (ref "J10") (pin "2") (pinfunction "2_2") (pintype "passive"))
      (node (ref "J2") (pin "44") (pinfunction "44_44") (pintype "passive"))
    )
    (net (code "110") (name "/PG7") (class "Default")
      (node (ref "J11") (pin "3") (pinfunction "3_3") (pintype "passive"))
      (node (ref "J2") (pin "43") (pinfunction "43_43") (pintype "passive"))
    )
    (net (code "111") (name "/PG8") (class "Default")
      (node (ref "J11") (pin "2") (pinfunction "2_2") (pintype "passive"))
      (node (ref "J2") (pin "42") (pinfunction "42_42") (pintype "passive"))
    )
    (net (code "112") (name "/PG9") (class "Default")
      (node (ref "J2") (pin "14") (pinfunction "14_14") (pintype "passive"))
    )
    (net (code "113") (name "/PG10") (class "Default")
      (node (ref "J2") (pin "15") (pinfunction "15_15") (pintype "passive"))
    )
    (net (code "114") (name "/PG11") (class "Default")
      (node (ref "IC2") (pin "16") (pinfunction "TXEN_16") (pintype "passive"))
      (node (ref "J2") (pin "16") (pinfunction "16_16") (pintype "passive"))
    )
    (net (code "115") (name "/PG12") (class "Default")
      (node (ref "J2") (pin "17") (pinfunction "17_17") (pintype "passive"))
    )
    (net (code "116") (name "/PG13") (class "Default")
      (node (ref "IC2") (pin "17") (pinfunction "TXD0_17") (pintype "passive"))
      (node (ref "J2") (pin "18") (pinfunction "18_18") (pintype "passive"))
    )
    (net (code "117") (name "/PG14") (class "Default")
      (node (ref "IC2") (pin "18") (pinfunction "TXD1_18") (pintype "passive"))
      (node (ref "J2") (pin "19") (pinfunction "19_19") (pintype "passive"))
    )
    (net (code "118") (name "/PG15") (class "Default")
      (node (ref "J2") (pin "20") (pinfunction "20_20") (pintype "passive"))
    )
    (net (code "119") (name "/RD_N") (class "Default")
      (node (ref "C23") (pin "2") (pinfunction "2_2") (pintype "passive"))
      (node (ref "IC2") (pin "22") (pinfunction "RXN_22") (pintype "passive"))
      (node (ref "R17") (pin "1") (pinfunction "1_1") (pintype "passive"))
      (node (ref "RJ1") (pin "6") (pinfunction "RD-_6") (pintype "passive"))
    )
    (net (code "120") (name "/RD_P") (class "Default")
      (node (ref "C22") (pin "2") (pinfunction "2_2") (pintype "passive"))
      (node (ref "IC2") (pin "23") (pinfunction "RXP_23") (pintype "passive"))
      (node (ref "R16") (pin "1") (pinfunction "1_1") (pintype "passive"))
      (node (ref "RJ1") (pin "3") (pinfunction "RD+_3") (pintype "passive"))
    )
    (net (code "121") (name "/RS232_RX") (class "Default")
      (node (ref "IC1") (pin "8") (pinfunction "R2IN_8") (pintype "passive"))
      (node (ref "J8") (pin "3") (pinfunction "3_3") (pintype "passive"))
    )
    (net (code "122") (name "/RS232_TX") (class "Default")
      (node (ref "IC1") (pin "7") (pinfunction "T2OUT_7") (pintype "passive"))
      (node (ref "J8") (pin "2") (pinfunction "2_2") (pintype "passive"))
    )
    (net (code "123") (name "/TD_N") (class "Default")
      (node (ref "C21") (pin "2") (pinfunction "2_2") (pintype "passive"))
      (node (ref "IC2") (pin "20") (pinfunction "TXN_20") (pintype "passive"))
      (node (ref "R15") (pin "1") (pinfunction "1_1") (pintype "passive"))
      (node (ref "RJ1") (pin "2") (pinfunction "TD-_2") (pintype "passive"))
    )
    (net (code "124") (name "/TD_P") (class "Default")
      (node (ref "C20") (pin "2") (pinfunction "2_2") (pintype "passive"))
      (node (ref "IC2") (pin "21") (pinfunction "TXP_21") (pintype "passive"))
      (node (ref "R14") (pin "1") (pinfunction "1_1") (pintype "passive"))
      (node (ref "RJ1") (pin "1") (pinfunction "TD+_1") (pintype "passive"))
    )
    (net (code "125") (name "GND") (class "Default")
      (node (ref "C1") (pin "2") (pinfunction "2_2") (pintype "passive"))
      (node (ref "C10") (pin "1") (pinfunction "1_1") (pintype "passive"))
      (node (ref "C11") (pin "2") (pinfunction "2_2") (pintype "passive"))
      (node (ref "C12") (pin "2") (pinfunction "2_2") (pintype "passive"))
      (node (ref "C13") (pin "1") (pinfunction "1_1") (pintype "passive"))
      (node (ref "C14") (pin "1") (pinfunction "1_1") (pintype "passive"))
      (node (ref "C15") (pin "1") (pinfunction "1_1") (pintype "passive"))
      (node (ref "C16") (pin "1") (pinfunction "1_1") (pintype "passive"))
      (node (ref "C17") (pin "1") (pinfunction "1_1") (pintype "passive"))
      (node (ref "C18") (pin "1") (pinfunction "1_1") (pintype "passive"))
      (node (ref "C19") (pin "1") (pinfunction "1_1") (pintype "passive"))
      (node (ref "C2") (pin "2") (pinfunction "2_2") (pintype "passive"))
      (node (ref "C20") (pin "1") (pinfunction "1_1") (pintype "passive"))
      (node (ref "C21") (pin "1") (pinfunction "1_1") (pintype "passive"))
      (node (ref "C22") (pin "1") (pinfunction "1_1") (pintype "passive"))
      (node (ref "C23") (pin "1") (pinfunction "1_1") (pintype "passive"))
      (node (ref "C24") (pin "1") (pinfunction "1_1") (pintype "passive"))
      (node (ref "C25") (pin "1") (pinfunction "1_1") (pintype "passive"))
      (node (ref "C26") (pin "1") (pinfunction "1_1") (pintype "passive"))
      (node (ref "C3") (pin "1") (pinfunction "1_1") (pintype "passive"))
      (node (ref "C6") (pin "1") (pinfunction "1_1") (pintype "passive"))
      (node (ref "C7") (pin "1") (pinfunction "1_1") (pintype "passive"))
      (node (ref "C8") (pin "2") (pinfunction "2_2") (pintype "passive"))
      (node (ref "C9") (pin "2") (pinfunction "2_2") (pintype "passive"))
      (node (ref "D1") (pin "1") (pinfunction "1_1") (pintype "passive"))
      (node (ref "D4") (pin "K") (pinfunction "K_K") (pintype "passive"))
      (node (ref "D5") (pin "K") (pinfunction "K_K") (pintype "passive"))
      (node (ref "D6") (pin "K") (pinfunction "K_K") (pintype "passive"))
      (node (ref "IC1") (pin "15") (pinfunction "GND_15") (pintype "passive"))
      (node (ref "IC2") (pin "25") (pinfunction "VSS_25") (pintype "passive"))
      (node (ref "IC3") (pin "1") (pinfunction "GND_1") (pintype "passive"))
      (node (ref "J1") (pin "31") (pinfunction "31_31") (pintype "passive"))
      (node (ref "J1") (pin "32") (pinfunction "32_32") (pintype "passive"))
      (node (ref "J10") (pin "1") (pinfunction "1_1") (pintype "passive"))
      (node (ref "J11") (pin "1") (pinfunction "1_1") (pintype "passive"))
      (node (ref "J16") (pin "3") (pinfunction "3_3") (pintype "passive"))
      (node (ref "J17") (pin "3") (pinfunction "3_3") (pintype "passive"))
      (node (ref "J18") (pin "3") (pinfunction "3_3") (pintype "passive"))
      (node (ref "J19") (pin "3") (pinfunction "3_3") (pintype "passive"))
      (node (ref "J2") (pin "30") (pinfunction "30_30") (pintype "passive"))
      (node (ref "J2") (pin "31") (pinfunction "31_31") (pintype "passive"))
      (node (ref "J3") (pin "1") (pinfunction "1_1") (pintype "passive"))
      (node (ref "J4") (pin "1") (pinfunction "1_1") (pintype "passive"))
      (node (ref "J5") (pin "1") (pinfunction "1_1") (pintype "passive"))
      (node (ref "J6") (pin "1") (pinfunction "1_1") (pintype "passive"))
      (node (ref "J7") (pin "1") (pinfunction "1_1") (pintype "passive"))
      (node (ref "J8") (pin "5") (pinfunction "5_5") (pintype "passive"))
      (node (ref "J9") (pin "1") (pinfunction "1_1") (pintype "passive"))
      (node (ref "P3") (pin "1") (pinfunction "1_1") (pintype "passive"))
      (node (ref "P3") (pin "2") (pinfunction "2_2") (pintype "passive"))
      (node (ref "P3") (pin "3") (pinfunction "3_3") (pintype "passive"))
      (node (ref "P3") (pin "4") (pinfunction "4_4") (pintype "passive"))
      (node (ref "P4") (pin "1") (pinfunction "1_1") (pintype "passive"))
      (node (ref "P4") (pin "2") (pinfunction "2_2") (pintype "passive"))
      (node (ref "P4") (pin "3") (pinfunction "3_3") (pintype "passive"))
      (node (ref "P4") (pin "4") (pinfunction "4_4") (pintype "passive"))
      (node (ref "Q1") (pin "2") (pinfunction "E_2") (pintype "passive"))
      (node (ref "R20") (pin "1") (pinfunction "1_1") (pintype "passive"))
      (node (ref "R21") (pin "1") (pinfunction "1_1") (pintype "passive"))
      (node (ref "R23") (pin "2") (pinfunction "2_2") (pintype "passive"))
      (node (ref "R24") (pin "2") (pinfunction "2_2") (pintype "passive"))
      (node (ref "R4") (pin "1") (pinfunction "1_1") (pintype "passive"))
      (node (ref "R5") (pin "1") (pinfunction "1_1") (pintype "passive"))
      (node (ref "RJ1") (pin "7") (pinfunction "NC_7") (pintype "passive"))
      (node (ref "RJ1") (pin "8") (pinfunction "NC_8") (pintype "passive"))
      (node (ref "RJ1") (pin "MH1") (pinfunction "MH1_MH1") (pintype "passive"))
      (node (ref "RJ1") (pin "MH2") (pinfunction "MH2_MH2") (pintype "passive"))
      (node (ref "RJ1") (pin "MH3") (pinfunction "MH3_MH3") (pintype "passive"))
      (node (ref "RJ1") (pin "MH4") (pinfunction "MH4_MH4") (pintype "passive"))
      (node (ref "SW1") (pin "2") (pinfunction "2_2") (pintype "passive"))
      (node (ref "SW2") (pin "2") (pinfunction "2_2") (pintype "passive"))
      (node (ref "U1") (pin "8") (pinfunction "GND_8") (pintype "passive"))
      (node (ref "U2") (pin "2") (pinfunction "GND_2") (pintype "passive"))
      (node (ref "U2") (pin "8") (pinfunction "RS_8") (pintype "passive"))
      (node (ref "U3") (pin "2") (pinfunction "GND_2") (pintype "passive"))
      (node (ref "U3") (pin "8") (pinfunction "RS_8") (pintype "passive"))
      (node (ref "X1") (pin "2") (pinfunction "GND_2") (pintype "passive"))
    )
    (net (code "126") (name "Net-(BUZZER1--)") (class "Default")
      (node (ref "BUZZER1") (pin "2") (pinfunction "-_2") (pintype "passive"))
      (node (ref "Q1") (pin "3") (pinfunction "C_3") (pintype "passive"))
    )
    (net (code "127") (name "Net-(C8-Pad1)") (class "Default")
      (node (ref "C8") (pin "1") (pinfunction "1_1") (pintype "passive"))
      (node (ref "R6") (pin "2") (pinfunction "2_2") (pintype "passive"))
      (node (ref "R8") (pin "1") (pinfunction "1_1") (pintype "passive"))
    )
    (net (code "128") (name "Net-(C9-Pad1)") (class "Default")
      (node (ref "C9") (pin "1") (pinfunction "1_1") (pintype "passive"))
      (node (ref "R7") (pin "1") (pinfunction "1_1") (pintype "passive"))
      (node (ref "R9") (pin "2") (pinfunction "2_2") (pintype "passive"))
    )
    (net (code "129") (name "Net-(C11-Pad1)") (class "Default")
      (node (ref "C11") (pin "1") (pinfunction "1_1") (pintype "passive"))
      (node (ref "R10") (pin "2") (pinfunction "2_2") (pintype "passive"))
      (node (ref "R12") (pin "1") (pinfunction "1_1") (pintype "passive"))
    )
    (net (code "130") (name "Net-(C12-Pad1)") (class "Default")
      (node (ref "C12") (pin "1") (pinfunction "1_1") (pintype "passive"))
      (node (ref "R11") (pin "1") (pinfunction "1_1") (pintype "passive"))
      (node (ref "R13") (pin "2") (pinfunction "2_2") (pintype "passive"))
    )
    (net (code "131") (name "Net-(D1-Pad2)") (class "Default")
      (node (ref "D1") (pin "2") (pinfunction "2_2") (pintype "passive"))
      (node (ref "J8") (pin "MH1") (pinfunction "MH1_MH1") (pintype "passive"))
      (node (ref "J8") (pin "MH2") (pinfunction "MH2_MH2") (pintype "passive"))
      (node (ref "R4") (pin "2") (pinfunction "2_2") (pintype "passive"))
    )
    (net (code "132") (name "Net-(D4-PadA)") (class "Default")
      (node (ref "D4") (pin "A") (pinfunction "A_A") (pintype "passive"))
      (node (ref "R19") (pin "1") (pinfunction "1_1") (pintype "passive"))
    )
    (net (code "133") (name "Net-(D5-PadA)") (class "Default")
      (node (ref "D5") (pin "A") (pinfunction "A_A") (pintype "passive"))
      (node (ref "R22") (pin "1") (pinfunction "1_1") (pintype "passive"))
    )
    (net (code "134") (name "Net-(D6-PadA)") (class "Default")
      (node (ref "D6") (pin "A") (pinfunction "A_A") (pintype "passive"))
      (node (ref "R25") (pin "1") (pinfunction "1_1") (pintype "passive"))
    )
    (net (code "135") (name "Net-(IC1-C1+)") (class "Default")
      (node (ref "C4") (pin "2") (pinfunction "2_2") (pintype "passive"))
      (node (ref "IC1") (pin "1") (pinfunction "C1+_1") (pintype "passive"))
    )
    (net (code "136") (name "Net-(IC1-C1-)") (class "Default")
      (node (ref "C4") (pin "1") (pinfunction "1_1") (pintype "passive"))
      (node (ref "IC1") (pin "3") (pinfunction "C1-_3") (pintype "passive"))
    )
    (net (code "137") (name "Net-(IC1-C2+)") (class "Default")
      (node (ref "C5") (pin "2") (pinfunction "2_2") (pintype "passive"))
      (node (ref "IC1") (pin "4") (pinfunction "C2+_4") (pintype "passive"))
    )
    (net (code "138") (name "Net-(IC1-C2-)") (class "Default")
      (node (ref "C5") (pin "1") (pinfunction "1_1") (pintype "passive"))
      (node (ref "IC1") (pin "5") (pinfunction "C2-_5") (pintype "passive"))
    )
    (net (code "139") (name "Net-(IC1-V+)") (class "Default")
      (node (ref "C6") (pin "2") (pinfunction "2_2") (pintype "passive"))
      (node (ref "IC1") (pin "2") (pinfunction "V+_2") (pintype "passive"))
    )
    (net (code "140") (name "Net-(IC1-V-)") (class "Default")
      (node (ref "C7") (pin "2") (pinfunction "2_2") (pintype "passive"))
      (node (ref "IC1") (pin "6") (pinfunction "V-_6") (pintype "passive"))
    )
    (net (code "141") (name "Net-(IC2-MDIO)") (class "Default")
      (node (ref "IC2") (pin "12") (pinfunction "MDIO_12") (pintype "passive"))
      (node (ref "R18") (pin "1") (pinfunction "1_1") (pintype "passive"))
    )
    (net (code "142") (name "Net-(IC2-RBIAS)") (class "Default")
      (node (ref "IC2") (pin "24") (pinfunction "RBIAS_24") (pintype "passive"))
      (node (ref "R24") (pin "1") (pinfunction "1_1") (pintype "passive"))
    )
    (net (code "143") (name "Net-(IC2-XTAL1{slash}CLKIN)") (class "Default")
      (node (ref "IC2") (pin "5") (pinfunction "XTAL1/CLKIN_5") (pintype "passive"))
      (node (ref "X1") (pin "3") (pinfunction "OSC2_3") (pintype "passive"))
    )
    (net (code "144") (name "Net-(IC2-XTAL2)") (class "Default")
      (node (ref "IC2") (pin "4") (pinfunction "XTAL2_4") (pintype "passive"))
      (node (ref "X1") (pin "1") (pinfunction "OSC1_1") (pintype "passive"))
    )
    (net (code "145") (name "Net-(Q1-B)") (class "Default")
      (node (ref "Q1") (pin "1") (pinfunction "B_1") (pintype "passive"))
      (node (ref "R3") (pin "2") (pinfunction "2_2") (pintype "passive"))
      (node (ref "R5") (pin "2") (pinfunction "2_2") (pintype "passive"))
    )
    (net (code "146") (name "Net-(RJ1-LED(Y)_A)") (class "Default")
      (node (ref "R20") (pin "2") (pinfunction "2_2") (pintype "passive"))
      (node (ref "RJ1") (pin "12") (pinfunction "LED(Y)_A_12") (pintype "passive"))
    )
    (net (code "147") (name "Net-(RJ1-LED(Y)_K)") (class "Default")
      (node (ref "R21") (pin "2") (pinfunction "2_2") (pintype "passive"))
      (node (ref "RJ1") (pin "11") (pinfunction "LED(Y)_K_11") (pintype "passive"))
    )
    (net (code "148") (name "VCC_3V3") (class "Default")
      (node (ref "IC2") (pin "9") (pinfunction "VDDIO_9") (pintype "passive"))
      (node (ref "J1") (pin "3") (pinfunction "3_3") (pintype "passive"))
      (node (ref "J1") (pin "4") (pinfunction "4_4") (pintype "passive"))
    )
    (net (code "149") (name "VCC_3V3E") (class "Default")
      (node (ref "C24") (pin "2") (pinfunction "2_2") (pintype "passive"))
      (node (ref "C25") (pin "2") (pinfunction "2_2") (pintype "passive"))
      (node (ref "C26") (pin "2") (pinfunction "2_2") (pintype "passive"))
      (node (ref "IC2") (pin "1") (pinfunction "VDD2A_1") (pintype "passive"))
      (node (ref "IC2") (pin "19") (pinfunction "VDD1A_19") (pintype "passive"))
      (node (ref "IC3") (pin "2") (pinfunction "VOUT_2") (pintype "passive"))
      (node (ref "R14") (pin "2") (pinfunction "2_2") (pintype "passive"))
      (node (ref "R15") (pin "2") (pinfunction "2_2") (pintype "passive"))
      (node (ref "R16") (pin "2") (pinfunction "2_2") (pintype "passive"))
      (node (ref "R17") (pin "2") (pinfunction "2_2") (pintype "passive"))
      (node (ref "RJ1") (pin "4") (pinfunction "TCT_4") (pintype "passive"))
      (node (ref "RJ1") (pin "5") (pinfunction "RCT_5") (pintype "passive"))
    )
    (net (code "150") (name "VCC_5V") (class "Default")
      (node (ref "C1") (pin "1") (pinfunction "1_1") (pintype "passive"))
      (node (ref "C10") (pin "2") (pinfunction "2_2") (pintype "passive"))
      (node (ref "C13") (pin "2") (pinfunction "2_2") (pintype "passive"))
      (node (ref "C15") (pin "2") (pinfunction "2_2") (pintype "passive"))
      (node (ref "C16") (pin "2") (pinfunction "2_2") (pintype "passive"))
      (node (ref "C18") (pin "2") (pinfunction "2_2") (pintype "passive"))
      (node (ref "C19") (pin "2") (pinfunction "2_2") (pintype "passive"))
      (node (ref "C2") (pin "1") (pinfunction "1_1") (pintype "passive"))
      (node (ref "C3") (pin "2") (pinfunction "2_2") (pintype "passive"))
      (node (ref "IC1") (pin "16") (pinfunction "VCC_16") (pintype "passive"))
      (node (ref "IC3") (pin "3") (pinfunction "VIN_3") (pintype "passive"))
      (node (ref "J1") (pin "1") (pinfunction "1_1") (pintype "passive"))
      (node (ref "J1") (pin "2") (pinfunction "2_2") (pintype "passive"))
      (node (ref "J10") (pin "4") (pinfunction "4_4") (pintype "passive"))
      (node (ref "J11") (pin "4") (pinfunction "4_4") (pintype "passive"))
      (node (ref "J3") (pin "4") (pinfunction "4_4") (pintype "passive"))
      (node (ref "J4") (pin "4") (pinfunction "4_4") (pintype "passive"))
      (node (ref "J5") (pin "4") (pinfunction "4_4") (pintype "passive"))
      (node (ref "J6") (pin "4") (pinfunction "4_4") (pintype "passive"))
      (node (ref "J7") (pin "4") (pinfunction "4_4") (pintype "passive"))
      (node (ref "J9") (pin "4") (pinfunction "4_4") (pintype "passive"))
      (node (ref "P2") (pin "1") (pinfunction "1_1") (pintype "passive"))
      (node (ref "P2") (pin "2") (pinfunction "2_2") (pintype "passive"))
      (node (ref "P2") (pin "3") (pinfunction "3_3") (pintype "passive"))
      (node (ref "P2") (pin "4") (pinfunction "4_4") (pintype "passive"))
      (node (ref "R1") (pin "2") (pinfunction "2_2") (pintype "passive"))
      (node (ref "R2") (pin "2") (pinfunction "2_2") (pintype "passive"))
      (node (ref "U1") (pin "1") (pinfunction "VCC_1") (pintype "passive"))
      (node (ref "U2") (pin "3") (pinfunction "VCC_3") (pintype "passive"))
      (node (ref "U3") (pin "3") (pinfunction "VCC_3") (pintype "passive"))
    )
    (net (code "151") (name "VCC_12V") (class "Default")
      (node (ref "BUZZER1") (pin "1") (pinfunction "+_1") (pintype "passive"))
      (node (ref "J16") (pin "1") (pinfunction "1_1") (pintype "passive"))
      (node (ref "J17") (pin "1") (pinfunction "1_1") (pintype "passive"))
      (node (ref "J18") (pin "1") (pinfunction "1_1") (pintype "passive"))
      (node (ref "J19") (pin "1") (pinfunction "1_1") (pintype "passive"))
      (node (ref "P1") (pin "1") (pinfunction "1_1") (pintype "passive"))
      (node (ref "P1") (pin "2") (pinfunction "2_2") (pintype "passive"))
      (node (ref "P1") (pin "3") (pinfunction "3_3") (pintype "passive"))
      (node (ref "P1") (pin "4") (pinfunction "4_4") (pintype "passive"))
    )
    (net (code "152") (name "unconnected-(IC1-R1IN-Pad13)") (class "Default")
      (node (ref "IC1") (pin "13") (pinfunction "R1IN_13") (pintype "passive+no_connect"))
    )
    (net (code "153") (name "unconnected-(IC1-R1OUT-Pad12)") (class "Default")
      (node (ref "IC1") (pin "12") (pinfunction "R1OUT_12") (pintype "passive+no_connect"))
    )
    (net (code "154") (name "unconnected-(IC1-T1IN-Pad11)") (class "Default")
      (node (ref "IC1") (pin "11") (pinfunction "T1IN_11") (pintype "passive+no_connect"))
    )
    (net (code "155") (name "unconnected-(IC1-T1OUT-Pad14)") (class "Default")
      (node (ref "IC1") (pin "14") (pinfunction "T1OUT_14") (pintype "passive+no_connect"))
    )
    (net (code "156") (name "unconnected-(IC2-RXER{slash}~{PHYAD0}-Pad10)") (class "Default")
      (node (ref "IC2") (pin "10") (pinfunction "RXER/~{PHYAD0}_10") (pintype "passive+no_connect"))
    )
    (net (code "157") (name "unconnected-(IC2-VDDCR-Pad6)") (class "Default")
      (node (ref "IC2") (pin "6") (pinfunction "VDDCR_6") (pintype "passive+no_connect"))
    )
    (net (code "158") (name "unconnected-(J8-Pad1)") (class "Default")
      (node (ref "J8") (pin "1") (pinfunction "1_1") (pintype "passive+no_connect"))
    )
    (net (code "159") (name "unconnected-(J8-Pad4)") (class "Default")
      (node (ref "J8") (pin "4") (pinfunction "4_4") (pintype "passive+no_connect"))
    )
    (net (code "160") (name "unconnected-(J8-Pad6)") (class "Default")
      (node (ref "J8") (pin "6") (pinfunction "6_6") (pintype "passive+no_connect"))
    )
    (net (code "161") (name "unconnected-(J8-Pad7)") (class "Default")
      (node (ref "J8") (pin "7") (pinfunction "7_7") (pintype "passive+no_connect"))
    )
    (net (code "162") (name "unconnected-(J8-Pad8)") (class "Default")
      (node (ref "J8") (pin "8") (pinfunction "8_8") (pintype "passive+no_connect"))
    )
    (net (code "163") (name "unconnected-(J8-Pad9)") (class "Default")
      (node (ref "J8") (pin "9") (pinfunction "9_9") (pintype "passive+no_connect"))
    )
    (net (code "164") (name "unconnected-(U1-D0-Pad2)") (class "Default")
      (node (ref "U1") (pin "2") (pinfunction "D0_2") (pintype "passive+no_connect"))
    )
    (net (code "165") (name "unconnected-(U1-D1-Pad3)") (class "Default")
      (node (ref "U1") (pin "3") (pinfunction "D1_3") (pintype "passive+no_connect"))
    )
    (net (code "166") (name "unconnected-(U1-D2-Pad4)") (class "Default")
      (node (ref "U1") (pin "4") (pinfunction "D2_4") (pintype "passive+no_connect"))
    )
    (net (code "167") (name "unconnected-(U1-D3-Pad5)") (class "Default")
      (node (ref "U1") (pin "5") (pinfunction "D3_5") (pintype "passive+no_connect"))
    )
    (net (code "168") (name "unconnected-(U1-D4-Pad6)") (class "Default")
      (node (ref "U1") (pin "6") (pinfunction "D4_6") (pintype "passive+no_connect"))
    )
    (net (code "169") (name "unconnected-(U1-D5-Pad7)") (class "Default")
      (node (ref "U1") (pin "7") (pinfunction "D5_7") (pintype "passive+no_connect"))
    )
    (net (code "170") (name "unconnected-(U1-RX-Pad13)") (class "Default")
      (node (ref "U1") (pin "13") (pinfunction "RX_13") (pintype "passive+no_connect"))
    )
    (net (code "171") (name "unconnected-(U1-SWCLK-Pad9)") (class "Default")
      (node (ref "U1") (pin "9") (pinfunction "SWCLK_9") (pintype "passive+no_connect"))
    )
    (net (code "172") (name "unconnected-(U1-SWDIO-Pad10)") (class "Default")
      (node (ref "U1") (pin "10") (pinfunction "SWDIO_10") (pintype "passive+no_connect"))
    )
    (net (code "173") (name "unconnected-(U1-TX-Pad14)") (class "Default")
      (node (ref "U1") (pin "14") (pinfunction "TX_14") (pintype "passive+no_connect"))
    )
    (net (code "174") (name "unconnected-(U2-Vref-Pad5)") (class "Default")
      (node (ref "U2") (pin "5") (pinfunction "Vref_5") (pintype "passive+no_connect"))
    )
    (net (code "175") (name "unconnected-(U3-Vref-Pad5)") (class "Default")
      (node (ref "U3") (pin "5") (pinfunction "Vref_5") (pintype "passive+no_connect"))
    )
  )
)
